# Hoja_Buck2.net
KiCad netlist of a schematic drawn in Altium Designer
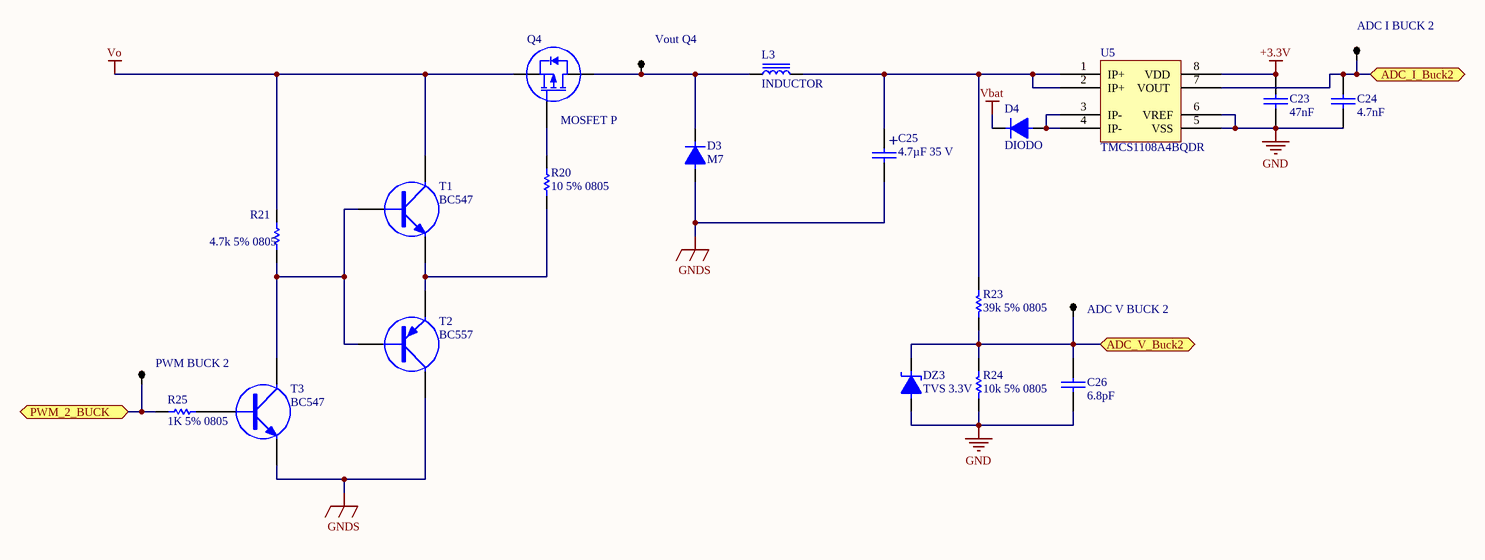
[diagram p0: Hoja_Buck2.SchDoc]

(export (version "E")
  (design (tool "Eeschema 10.0.6"))
  (components
    (comp (ref "ADC I BUCK 2") (value "~") (footprint "TPTH") (libsource (lib "Libreria_Casera") (part "TP")))
    (comp (ref "ADC V BUCK 2") (value "~") (footprint "TPTH") (libsource (lib "Libreria_Casera") (part "TP")))
    (comp (ref "C23") (value "47nF") (footprint "0805") (libsource (lib "Libreria_Casera") (part "CAP")))
    (comp (ref "C24") (value "4.7nF") (footprint "0805") (libsource (lib "Libreria_Casera") (part "CAP")))
    (comp (ref "C25")
      (value "4.7µF 35 V")
      (footprint "CAPSMD8x8.3")
      (libsource (lib "Libreria_Casera") (part "CAPPOL"))
    )
    (comp (ref "C26") (value "6.8pF") (footprint "0805") (libsource (lib "Libreria_Casera") (part "CAP")))
    (comp (ref "D3")
      (value "M7")
      (footprint "DO-214AC")
      (description "Diodos Estándar 1000 V 1A Montaje en superficie SMA")
      (libsource (lib "Libreria_Casera") (part "DIODO"))
    )
    (comp (ref "D4") (value "DIODO") (footprint "SOD123") (libsource (lib "Libreria_Casera") (part "DIODO")))
    (comp (ref "DZ3")
      (value "TVS 3.3V")
      (footprint "sod123")
      (libsource (lib "Libreria_Casera") (part "DIODO ZENER"))
    )
    (comp (ref "L3")
      (value "INDUCTOR")
      (footprint "IND_HCTI-220-5.8:IND_HCTI-220-5.8")
      (libsource (lib "Libreria_Casera") (part "INDUCTOR"))
    )
    (comp (ref "PWM BUCK 2") (value "~") (footprint "TPTH") (libsource (lib "Libreria_Casera") (part "TP")))
    (comp (ref "Q4")
      (value "MOSFET P")
      (footprint "TO-220 V")
      (libsource (lib "Libreria_Casera") (part "MOSFET P"))
    )
    (comp (ref "R20")
      (value "10 5% 0805")
      (footprint "0805")
      (libsource (lib "Libreria_Casera") (part "RES"))
    )
    (comp (ref "R21")
      (value "4.7k 5% 0805")
      (footprint "0805")
      (libsource (lib "Libreria_Casera") (part "RES"))
    )
    (comp (ref "R23")
      (value "39k 5% 0805")
      (footprint "0805")
      (libsource (lib "Libreria_Casera") (part "RES"))
    )
    (comp (ref "R24")
      (value "10k 5% 0805")
      (footprint "0805")
      (libsource (lib "Libreria_Casera") (part "RES"))
    )
    (comp (ref "R25")
      (value "1K 5% 0805")
      (footprint "0805")
      (libsource (lib "Libreria_Casera") (part "RES"))
    )
    (comp (ref "T1")
      (value "BC547")
      (footprint "SOT23-3")
      (description "Transistores - Bipolar (BJT) - Simple NPN 45 V 100 mA 300MHz 500 mW Orificio pasante TO-92-3")
      (libsource (lib "Libreria_Casera") (part "TRANSISTOR NPN"))
    )
    (comp (ref "T2")
      (value "BC557")
      (footprint "SOT23-3")
      (description "Transistores - Bipolar (BJT) - Simple PNP 45 V 100 mA 150MHz 500 mW Orificio pasante TO-92-3")
      (libsource (lib "Libreria_Casera") (part "TRANSISTOR PNP"))
    )
    (comp (ref "T3")
      (value "BC547")
      (footprint "SOT23-3")
      (description "Transistores - Bipolar (BJT) - Simple NPN 45 V 100 mA 300MHz 500 mW Orificio pasante TO-92-3")
      (libsource (lib "Libreria_Casera") (part "TRANSISTOR NPN"))
    )
    (comp (ref "U5")
      (value "TMCS1108A4BQDR")
      (footprint "SOIC8")
      (description "Sensores de corriente 1 canal Efecto Hall Bidireccional 8-SOIC (ancho 0.154\", 3.90mm)")
      (libsource (lib "Libreria_Casera") (part "MLX91221KDC"))
    )
    (comp (ref "Vout Q4")
      (value "Vout Q4")
      (footprint "TPTH")
      (libsource (lib "Libreria_Casera") (part "TP"))
    )
  )
  (nets
    (net (code "1") (name "+3.3V") (class "Default")
      (node (ref "C23") (pin "1") (pinfunction "1_1") (pintype "passive"))
      (node (ref "U5") (pin "8") (pinfunction "VDD_8") (pintype "passive"))
    )
    (net (code "2") (name "/ADC_I_Buck2") (class "Default")
      (node (ref "ADC I BUCK 2") (pin "1") (pinfunction "1_1") (pintype "passive"))
      (node (ref "C24") (pin "1") (pinfunction "1_1") (pintype "passive"))
      (node (ref "U5") (pin "7") (pinfunction "VOUT_7") (pintype "passive"))
    )
    (net (code "3") (name "/ADC_V_Buck2") (class "Default")
      (node (ref "ADC V BUCK 2") (pin "1") (pinfunction "1_1") (pintype "passive"))
      (node (ref "C26") (pin "1") (pinfunction "1_1") (pintype "passive"))
      (node (ref "DZ3") (pin "2") (pinfunction "2_2") (pintype "passive"))
      (node (ref "R23") (pin "1") (pinfunction "1_1") (pintype "passive"))
      (node (ref "R24") (pin "2") (pinfunction "2_2") (pintype "passive"))
    )
    (net (code "4") (name "/PWM_2_BUCK") (class "Default")
      (node (ref "PWM BUCK 2") (pin "1") (pinfunction "1_1") (pintype "passive"))
      (node (ref "R25") (pin "1") (pinfunction "1_1") (pintype "passive"))
    )
    (net (code "5") (name "GND") (class "Default")
      (node (ref "C23") (pin "2") (pinfunction "2_2") (pintype "passive"))
      (node (ref "C24") (pin "2") (pinfunction "2_2") (pintype "passive"))
      (node (ref "C26") (pin "2") (pinfunction "2_2") (pintype "passive"))
      (node (ref "DZ3") (pin "1") (pinfunction "1_1") (pintype "passive"))
      (node (ref "R24") (pin "1") (pinfunction "1_1") (pintype "passive"))
      (node (ref "U5") (pin "5") (pinfunction "VSS_5") (pintype "passive"))
      (node (ref "U5") (pin "6") (pinfunction "VREF_6") (pintype "passive"))
    )
    (net (code "6") (name "GNDS") (class "Default")
      (node (ref "C25") (pin "2") (pinfunction "2_2") (pintype "passive"))
      (node (ref "D3") (pin "1") (pinfunction "1_1") (pintype "passive"))
      (node (ref "T2") (pin "2") (pinfunction "C_2") (pintype "passive"))
      (node (ref "T3") (pin "3") (pinfunction "E_3") (pintype "passive"))
    )
    (net (code "7") (name "Net-(C25-Pad1)") (class "Default")
      (node (ref "C25") (pin "1") (pinfunction "1_1") (pintype "passive"))
      (node (ref "L3") (pin "2") (pinfunction "2_2") (pintype "passive"))
      (node (ref "R23") (pin "2") (pinfunction "2_2") (pintype "passive"))
      (node (ref "U5") (pin "1") (pinfunction "IP+_1") (pintype "passive"))
      (node (ref "U5") (pin "2") (pinfunction "IP+_2") (pintype "passive"))
    )
    (net (code "8") (name "Net-(D4-Pad1)") (class "Default")
      (node (ref "D4") (pin "1") (pinfunction "1_1") (pintype "passive"))
      (node (ref "U5") (pin "3") (pinfunction "IP-_3") (pintype "passive"))
      (node (ref "U5") (pin "4") (pinfunction "IP-_4") (pintype "passive"))
    )
    (net (code "9") (name "Net-(Q4-D)") (class "Default")
      (node (ref "D3") (pin "2") (pinfunction "2_2") (pintype "passive"))
      (node (ref "L3") (pin "1") (pinfunction "1_1") (pintype "passive"))
      (node (ref "Q4") (pin "2") (pinfunction "D_2") (pintype "passive"))
      (node (ref "Vout Q4") (pin "1") (pinfunction "1_1") (pintype "passive"))
    )
    (net (code "10") (name "Net-(Q4-G)") (class "Default")
      (node (ref "Q4") (pin "1") (pinfunction "G_1") (pintype "passive"))
      (node (ref "R20") (pin "1") (pinfunction "1_1") (pintype "passive"))
    )
    (net (code "11") (name "Net-(T1-B)") (class "Default")
      (node (ref "R21") (pin "2") (pinfunction "2_2") (pintype "passive"))
      (node (ref "T1") (pin "1") (pinfunction "B_1") (pintype "passive"))
      (node (ref "T2") (pin "1") (pinfunction "B_1") (pintype "passive"))
      (node (ref "T3") (pin "2") (pinfunction "C_2") (pintype "passive"))
    )
    (net (code "12") (name "Net-(T1-E)") (class "Default")
      (node (ref "R20") (pin "2") (pinfunction "2_2") (pintype "passive"))
      (node (ref "T1") (pin "3") (pinfunction "E_3") (pintype "passive"))
      (node (ref "T2") (pin "3") (pinfunction "E_3") (pintype "passive"))
    )
    (net (code "13") (name "Net-(T3-B)") (class "Default")
      (node (ref "R25") (pin "2") (pinfunction "2_2") (pintype "passive"))
      (node (ref "T3") (pin "1") (pinfunction "B_1") (pintype "passive"))
    )
    (net (code "14") (name "Vbat") (class "Default")
      (node (ref "D4") (pin "2") (pinfunction "2_2") (pintype "passive"))
    )
    (net (code "15") (name "Vo") (class "Default")
      (node (ref "Q4") (pin "3") (pinfunction "S_3") (pintype "passive"))
      (node (ref "R21") (pin "1") (pinfunction "1_1") (pintype "passive"))
      (node (ref "T1") (pin "2") (pinfunction "C_2") (pintype "passive"))
    )
  )
)
